# Principal.net
KiCad netlist of a schematic drawn in Altium Designer
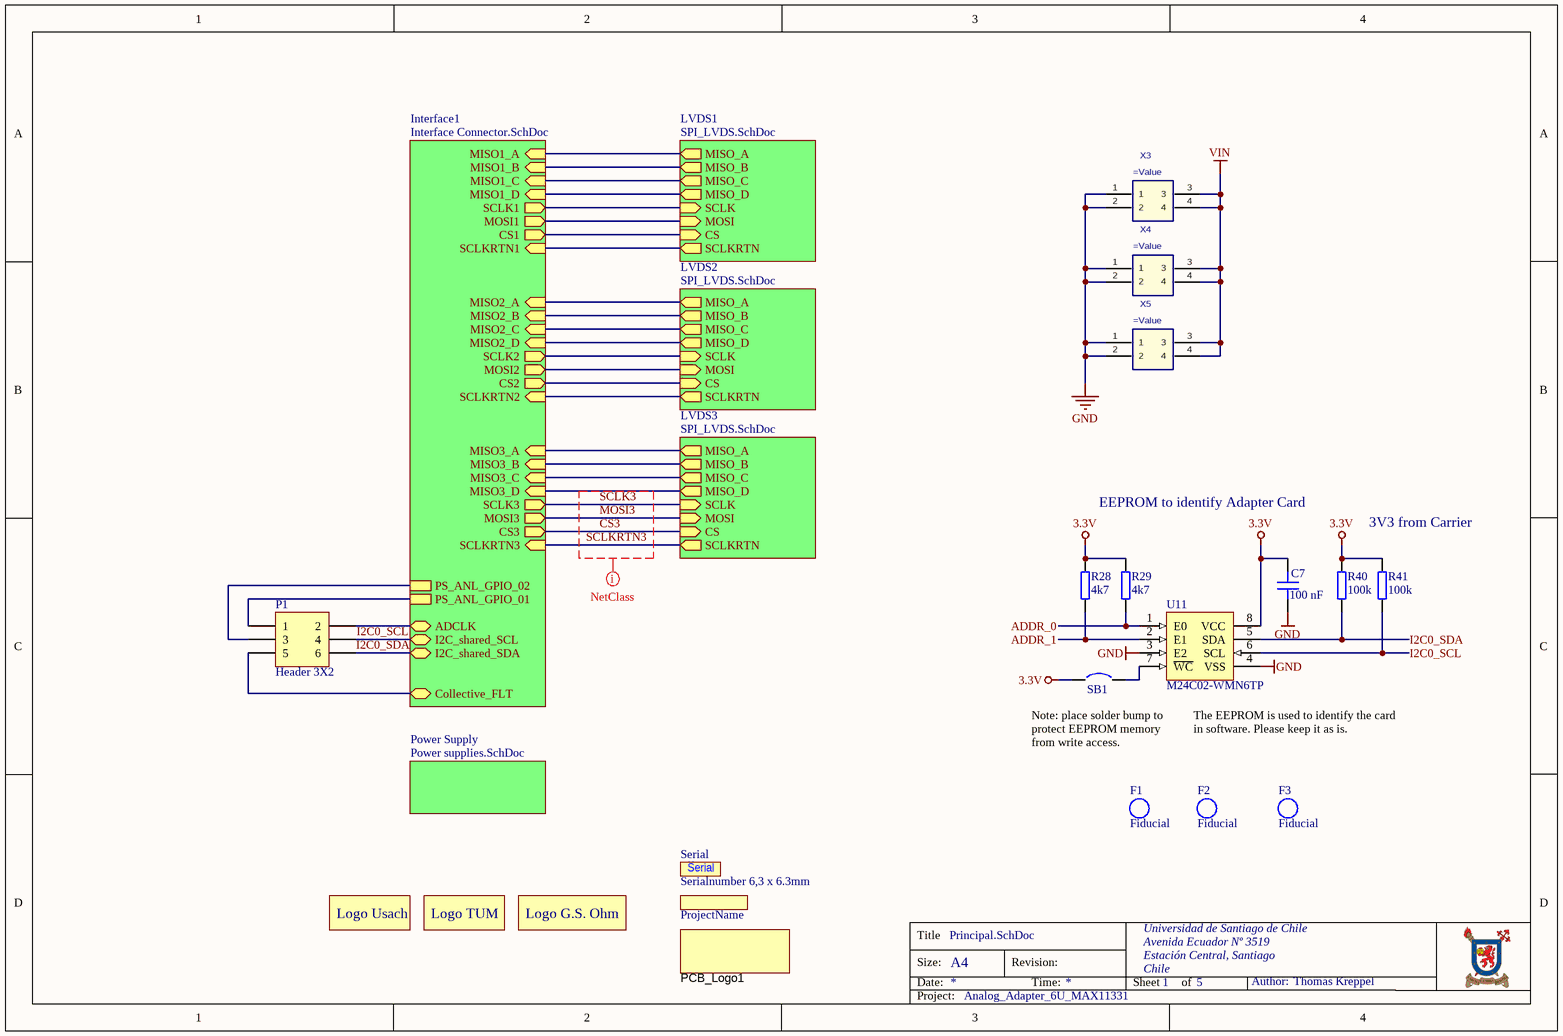
[diagram p0: Principal.SchDoc]

(export (version "E")
  (design (tool "Eeschema 10.0.6"))
  (components
    (comp (ref "C7")
      (value "100 nF")
      (footprint "C_0603")
      (description "Capacitor 0603, 6.3 VDC, 100 nF, X5R")
      (fields
        (field (name "MANUFACTURER PART NUMBER") "C0603C104K9PACTU")
        (field (name "MANUFACTURER") "KEMET")
        (field (name "CREATED FROM") "MGremer")
      )
      (libsource (lib "user") (part "Capacitor"))
    )
    (comp (ref "F1")
      (value "Fiducial")
      (footprint "Fiducial_1.7mm")
      (description "Fiducial for Assembler")
      (libsource (lib "Componentes_SOC") (part "Fiducial"))
    )
    (comp (ref "F2")
      (value "Fiducial")
      (footprint "Fiducial_1.7mm")
      (description "Fiducial for Assembler")
      (libsource (lib "Componentes_SOC") (part "Fiducial"))
    )
    (comp (ref "F3")
      (value "Fiducial")
      (footprint "Fiducial_1.7mm")
      (description "Fiducial for Assembler")
      (libsource (lib "Componentes_SOC") (part "Fiducial"))
    )
    (comp (ref "Logo1")
      (value "LOGO USACH")
      (footprint "Logo Usach")
      (libsource (lib "Componentes_SOC") (part "LOGO USACH"))
    )
    (comp (ref "Logo2")
      (value "LOGO TUM")
      (footprint "Logo TUM")
      (libsource (lib "Componentes_SOC") (part "LOGO TUM"))
    )
    (comp (ref "Logo3")
      (value "LOGO G.S. Ohm")
      (footprint "Logo G.S.Ohm University")
      (libsource (lib "Componentes_SOC") (part "LOGO G.S. Ohm"))
    )
    (comp (ref "P1")
      (value "Header 3X2")
      (footprint "HDR2X3")
      (description "Header, 3-Pin, Dual row")
      (fields (field (name "PUBLISHER") "Altium Limited"))
      (libsource (lib "Miscellaneous Connectors") (part "Header 3X2"))
    )
    (comp (ref "PCB_Logo1")
      (value "ESD Susceptible")
      (footprint "ESD_Overlay_Medium")
      (description "ESD Susceptible Symbol")
      (fields (field (name "CREATED") "2018_11_25_AGeiger"))
      (libsource (lib "Componentes_SOC") (part "LOGO_ESD_Susceptible"))
    )
    (comp (ref "ProjectName")
      (value "Project Name, Rev")
      (footprint "ID_ProjectRev")
      (description "Project Name and Revision Number")
      (fields (field (name "CREATED") "2018_11_23_AGeiger"))
      (libsource (lib "Componentes_SOC") (part "ID_ProjectRev"))
    )
    (comp (ref "R28")
      (value "4k7")
      (footprint "RES 0603_1608")
      (description "SMD resistor E24 series")
      (fields
        (field (name "MANUFACTURER PART NUMBER") "0603WAF4701T5E")
        (field (name "MANUFACTURER") "UNI-ROYAL")
        (field (name "CREATED FROM") "AGeiger")
      )
      (libsource (lib "user") (part "Resistor"))
    )
    (comp (ref "R29")
      (value "4k7")
      (footprint "RES 0603_1608")
      (description "SMD resistor E24 series")
      (fields
        (field (name "MANUFACTURER PART NUMBER") "0603WAF4701T5E")
        (field (name "MANUFACTURER") "UNI-ROYAL")
        (field (name "CREATED FROM") "AGeiger")
      )
      (libsource (lib "user") (part "Resistor"))
    )
    (comp (ref "R40")
      (value "100k")
      (footprint "RES 0603_1608")
      (description "SMD resistor E24 series")
      (fields
        (field (name "MANUFACTURER PART NUMBER") "RK73B1JTTD104J")
        (field (name "MANUFACTURER") "KOA Speer")
        (field (name "CREATED FROM") "MGremer")
      )
      (libsource (lib "user") (part "Resistor"))
    )
    (comp (ref "R41")
      (value "100k")
      (footprint "RES 0603_1608")
      (description "SMD resistor E24 series")
      (fields
        (field (name "MANUFACTURER PART NUMBER") "RK73B1JTTD104J")
        (field (name "MANUFACTURER") "KOA Speer")
        (field (name "CREATED FROM") "MGremer")
      )
      (libsource (lib "user") (part "Resistor"))
    )
    (comp (ref "SB1")
      (value "Solder Bump 0603")
      (footprint "SB_0603")
      (fields (field (name "CREATED FROM") "AGeiger"))
      (libsource (lib "user") (part "Solder_Bump"))
    )
    (comp (ref "Serial")
      (value "Serialnumber 6,3 x 6.3mm")
      (footprint "Serial_6.3x6.3mm")
      (fields (field (name "CREATED") "2018_09_18_AGeiger"))
      (libsource (lib "Componentes_SOC") (part "SerialNumber"))
    )
    (comp (ref "U11")
      (value "M24C02-WMN6TP")
      (footprint "D0008A_N")
      (description "2Kbit I2C SOP-8 EEPROM ROHS")
      (fields
        (field (name "MANUFACTURER") "STMicroelectronics")
        (field (name "LCSC PART NUMBER") "C7562")
        (field (name "CREATED FROM") "AGeiger")
      )
      (libsource (lib "user") (part "M24256"))
    )
    (comp (ref "X3")
      (value "~")
      (footprint "IPL1-102-01-L-D-K")
      (description "2.54mm Double Row Terminal Assembly, Right-Angled")
      (fields (field (name "MF") "SAMTEC") (field (name "CREATED") "2018_05_02_AGeiger"))
      (libsource (lib "Componentes_SOC") (part "IPL1-102-XX-X-D-X"))
    )
    (comp (ref "X4")
      (value "~")
      (footprint "IPL1-102-01-L-D-K")
      (description "2.54mm Double Row Terminal Assembly, Right-Angled")
      (fields (field (name "MF") "SAMTEC") (field (name "CREATED") "2018_05_02_AGeiger"))
      (libsource (lib "Componentes_SOC") (part "IPL1-102-XX-X-D-X"))
    )
    (comp (ref "X5")
      (value "~")
      (footprint "IPL1-102-01-L-D-K")
      (description "2.54mm Double Row Terminal Assembly, Right-Angled")
      (fields (field (name "MF") "SAMTEC") (field (name "CREATED") "2018_05_02_AGeiger"))
      (libsource (lib "Componentes_SOC") (part "IPL1-102-XX-X-D-X"))
    )
  )
  (nets
    (net (code "1") (name "/ADCLK") (class "Default")
      (node (ref "P1") (pin "2") (pinfunction "2_2") (pintype "passive"))
    )
    (net (code "2") (name "/ADDR_0") (class "Default")
      (node (ref "R29") (pin "1") (pinfunction "1_1") (pintype "passive"))
      (node (ref "U11") (pin "1") (pinfunction "E0_1") (pintype "input"))
    )
    (net (code "3") (name "/ADDR_1") (class "Default")
      (node (ref "R28") (pin "1") (pinfunction "1_1") (pintype "passive"))
      (node (ref "U11") (pin "2") (pinfunction "E1_2") (pintype "input"))
    )
    (net (code "7") (name "/Collective_FLT") (class "Default")
      (node (ref "P1") (pin "5") (pinfunction "5_5") (pintype "passive"))
    )
    (net (code "8") (name "/I2C0_SCL") (class "Default")
      (node (ref "P1") (pin "4") (pinfunction "4_4") (pintype "passive"))
      (node (ref "R41") (pin "1") (pinfunction "1_1") (pintype "passive"))
      (node (ref "U11") (pin "6") (pinfunction "SCL_6") (pintype "input"))
    )
    (net (code "9") (name "/I2C0_SDA") (class "Default")
      (node (ref "P1") (pin "6") (pinfunction "6_6") (pintype "passive"))
      (node (ref "R40") (pin "1") (pinfunction "1_1") (pintype "passive"))
      (node (ref "U11") (pin "5") (pinfunction "SDA_5") (pintype "open_collector"))
    )
    (net (code "25") (name "/PS_ANL_GPIO_01") (class "Default")
      (node (ref "P1") (pin "1") (pinfunction "1_1") (pintype "passive"))
    )
    (net (code "26") (name "/PS_ANL_GPIO_02") (class "Default")
      (node (ref "P1") (pin "3") (pinfunction "3_3") (pintype "passive"))
    )
    (net (code "33") (name "3.3V") (class "Default")
      (node (ref "C7") (pin "1") (pinfunction "1_1") (pintype "passive"))
      (node (ref "R28") (pin "2") (pinfunction "2_2") (pintype "passive"))
      (node (ref "R29") (pin "2") (pinfunction "2_2") (pintype "passive"))
      (node (ref "R40") (pin "2") (pinfunction "2_2") (pintype "passive"))
      (node (ref "R41") (pin "2") (pinfunction "2_2") (pintype "passive"))
      (node (ref "SB1") (pin "1") (pinfunction "1_1") (pintype "passive"))
      (node (ref "U11") (pin "8") (pinfunction "VCC_8") (pintype "power_in"))
    )
    (net (code "34") (name "GND") (class "Default")
      (node (ref "C7") (pin "2") (pinfunction "2_2") (pintype "passive"))
      (node (ref "U11") (pin "3") (pinfunction "E2_3") (pintype "input"))
      (node (ref "U11") (pin "4") (pinfunction "VSS_4") (pintype "power_in"))
      (node (ref "X3") (pin "1") (pinfunction "1_1") (pintype "passive"))
      (node (ref "X3") (pin "2") (pinfunction "2_2") (pintype "passive"))
      (node (ref "X4") (pin "1") (pinfunction "1_1") (pintype "passive"))
      (node (ref "X4") (pin "2") (pinfunction "2_2") (pintype "passive"))
      (node (ref "X5") (pin "1") (pinfunction "1_1") (pintype "passive"))
      (node (ref "X5") (pin "2") (pinfunction "2_2") (pintype "passive"))
    )
    (net (code "35") (name "Net-(U11-~{WC})") (class "Default")
      (node (ref "SB1") (pin "2") (pinfunction "2_2") (pintype "passive"))
      (node (ref "U11") (pin "7") (pinfunction "~{WC}_7") (pintype "input"))
    )
    (net (code "36") (name "VIN") (class "Default")
      (node (ref "X3") (pin "3") (pinfunction "3_3") (pintype "passive"))
      (node (ref "X3") (pin "4") (pinfunction "4_4") (pintype "passive"))
      (node (ref "X4") (pin "3") (pinfunction "3_3") (pintype "passive"))
      (node (ref "X4") (pin "4") (pinfunction "4_4") (pintype "passive"))
      (node (ref "X5") (pin "3") (pinfunction "3_3") (pintype "passive"))
      (node (ref "X5") (pin "4") (pinfunction "4_4") (pintype "passive"))
    )
  )
)
